# design.net
KiCad netlist of a schematic drawn in Altium Designer
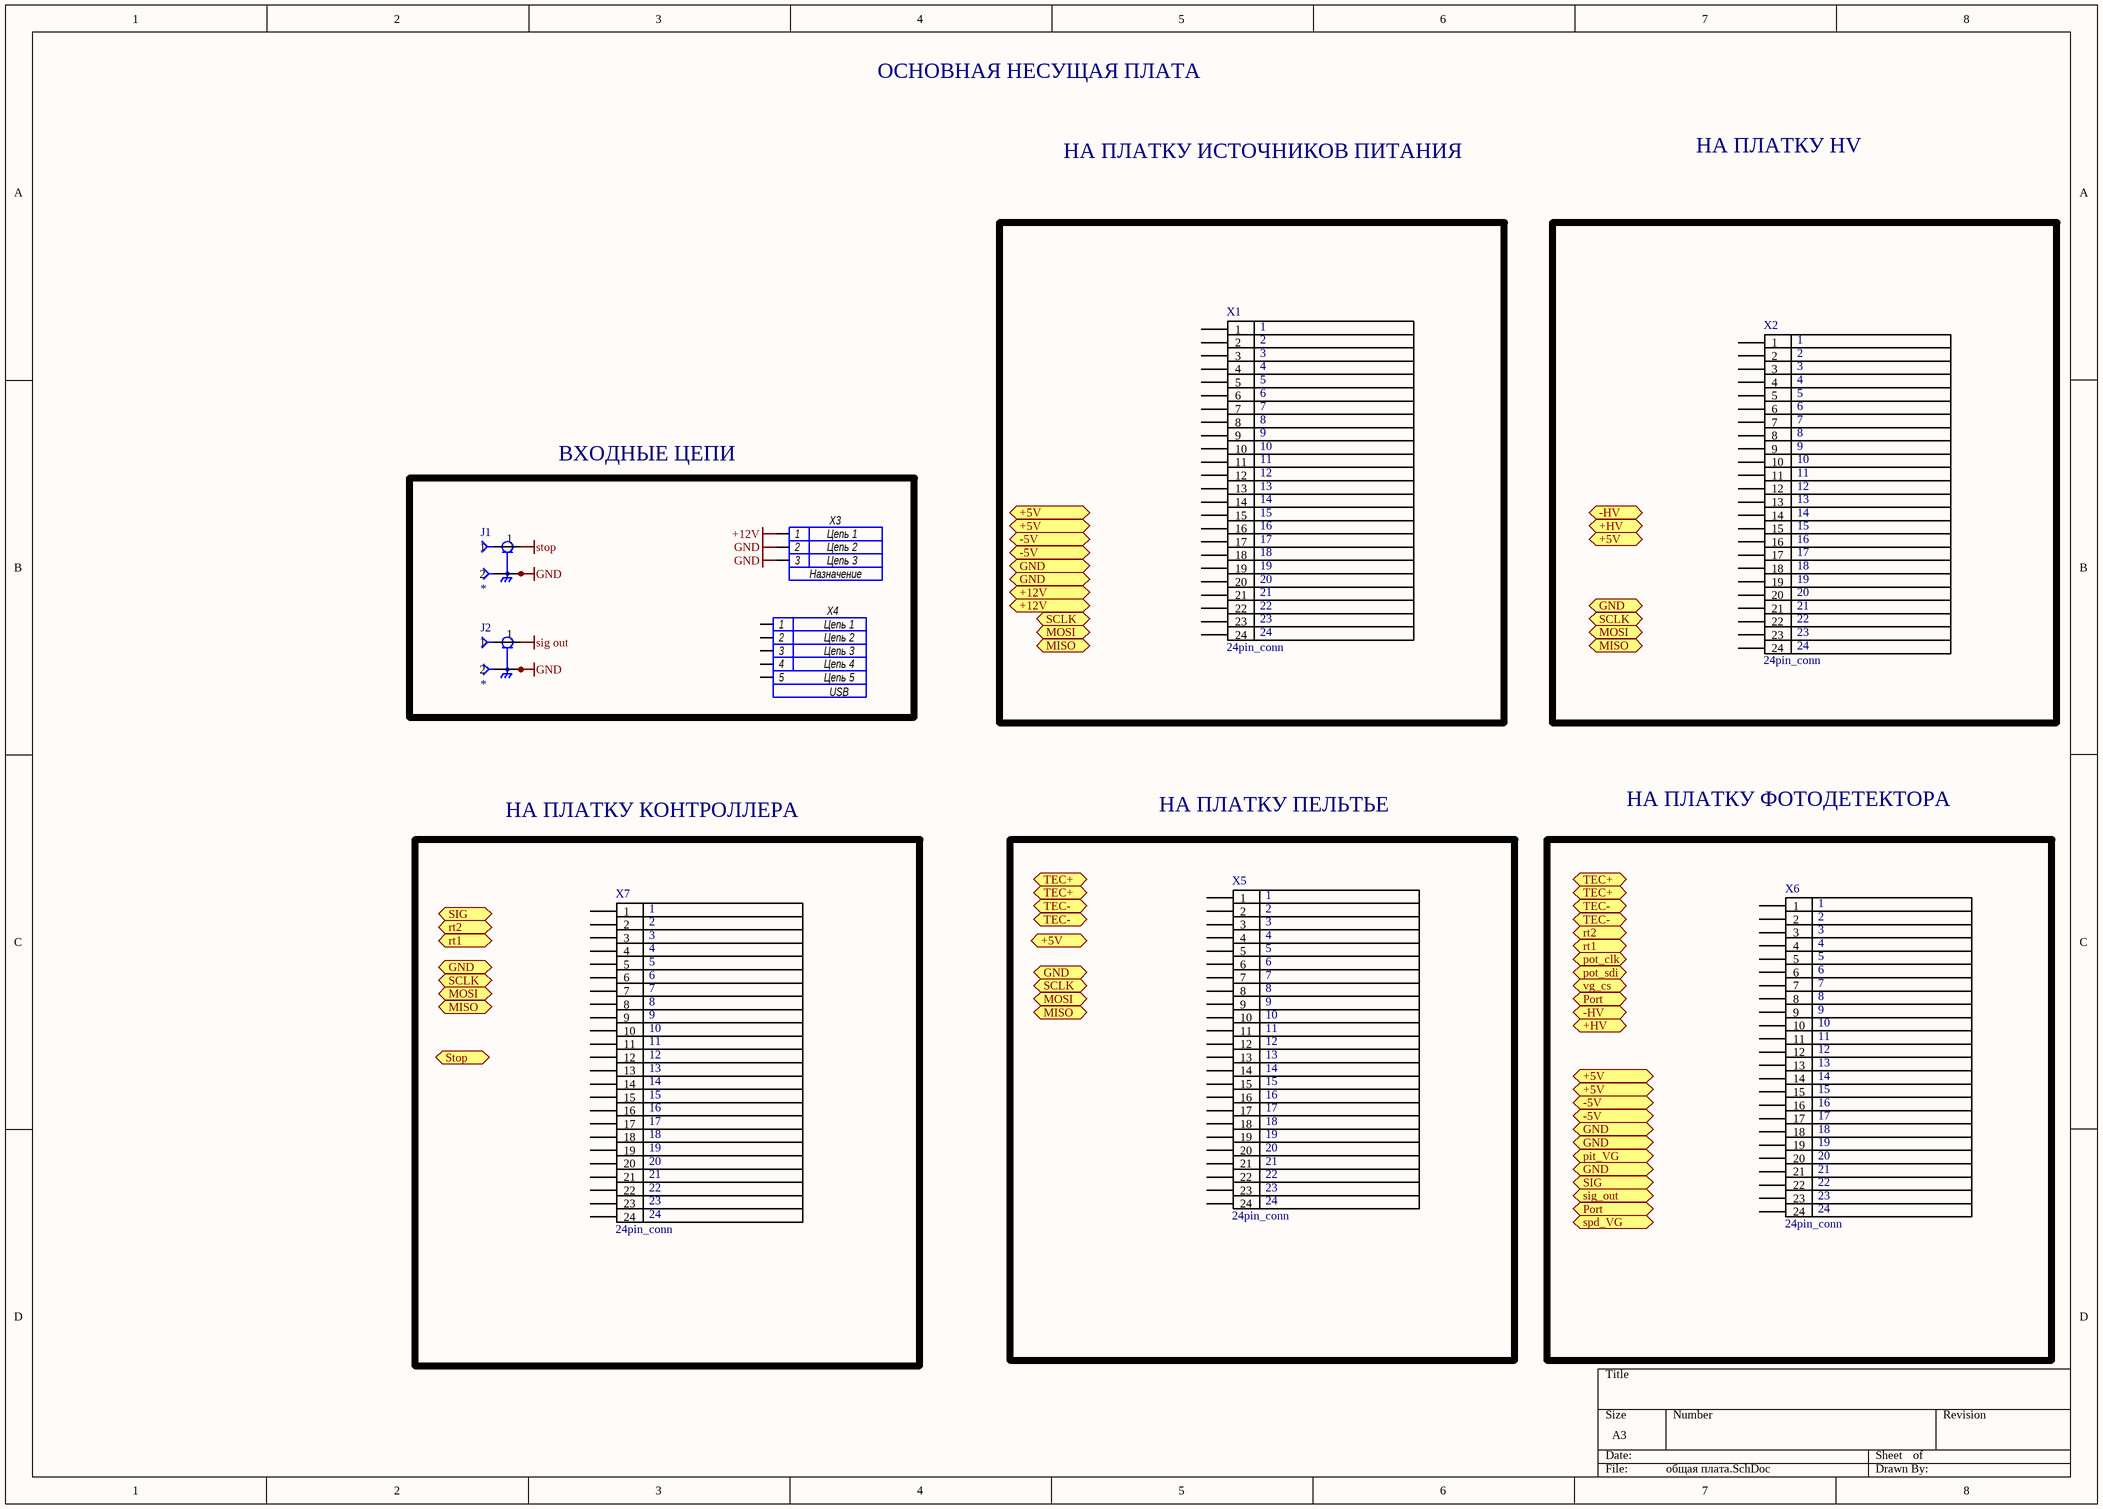
[diagram p0: общая плата.SchDoc]

(export (version "E")
  (design (tool "Eeschema 10.0.6"))
  (components
    (comp (ref "J1")
      (value "221790-1")
      (footprint "TE_221790-1")
      (description "Connector; SMA; PCB; Right Angle; Stainless Steel; 0.6 in.; Beryllium Copper")
      (fields (field (name "MF") "TE Connectivity") (field (name "COMMENT_1") "*"))
      (libsource (lib "SMA 221790-1") (part "221790-1"))
    )
    (comp (ref "J2")
      (value "221790-1")
      (footprint "TE_221790-1")
      (description "Connector; SMA; PCB; Right Angle; Stainless Steel; 0.6 in.; Beryllium Copper")
      (fields (field (name "MF") "TE Connectivity") (field (name "COMMENT_1") "*"))
      (libsource (lib "SMA 221790-1") (part "221790-1"))
    )
    (comp (ref "X1") (value "24pin_conn") (footprint "BH-24") (libsource (lib "Schlib1") (part "24pin_conn")))
    (comp (ref "X2") (value "24pin_conn") (footprint "BH-24") (libsource (lib "Schlib1") (part "24pin_conn")))
    (comp (ref "X3")
      (value "Model")
      (footprint "DC210")
      (fields
        (field (name "NET1") "Цепь 1")
        (field (name "NET2") "Цепь 2")
        (field (name "NAME") "Назначение")
        (field (name "NET3") "Цепь 3")
      )
      (libsource (lib "SCH_LIB") (part "Connector 3"))
    )
    (comp (ref "X4")
      (value "Model")
      (footprint "USB_TypeB")
      (fields
        (field (name "NET4") "Цепь 4")
        (field (name "NET1") "Цепь 1")
        (field (name "NET2") "Цепь 2")
        (field (name "NAME") "USB")
        (field (name "NET3") "Цепь 3")
        (field (name "NET5") "Цепь 5")
      )
      (libsource (lib "SCH_LIB") (part "Connector 5"))
    )
    (comp (ref "X5") (value "24pin_conn") (footprint "BH-24") (libsource (lib "Schlib1") (part "24pin_conn")))
    (comp (ref "X6") (value "24pin_conn") (footprint "BH-24") (libsource (lib "Schlib1") (part "24pin_conn")))
    (comp (ref "X7") (value "24pin_conn") (footprint "BH-24") (libsource (lib "Schlib1") (part "24pin_conn")))
  )
  (nets
    (net (code "1") (name "+12V") (class "Default")
      (node (ref "X3") (pin "1") (pinfunction "1_1") (pintype "passive"))
    )
    (net (code "22") (name "GND") (class "Default")
      (node (ref "J1") (pin "2") (pinfunction "2_2") (pintype "passive"))
      (node (ref "J1") (pin "3") (pinfunction "2_3") (pintype "passive"))
      (node (ref "J1") (pin "4") (pinfunction "2_4") (pintype "passive"))
      (node (ref "J1") (pin "5") (pinfunction "2_5") (pintype "passive"))
      (node (ref "J2") (pin "2") (pinfunction "2_2") (pintype "passive"))
      (node (ref "J2") (pin "3") (pinfunction "2_3") (pintype "passive"))
      (node (ref "J2") (pin "4") (pinfunction "2_4") (pintype "passive"))
      (node (ref "J2") (pin "5") (pinfunction "2_5") (pintype "passive"))
      (node (ref "X3") (pin "2") (pinfunction "2_2") (pintype "passive"))
      (node (ref "X3") (pin "3") (pinfunction "3_3") (pintype "passive"))
    )
    (net (code "23") (name "sig out") (class "Default")
      (node (ref "J2") (pin "1") (pinfunction "1_1") (pintype "passive"))
    )
    (net (code "24") (name "stop") (class "Default")
      (node (ref "J1") (pin "1") (pinfunction "1_1") (pintype "passive"))
    )
    (net (code "25") (name "unconnected-(X1-Pad1)") (class "Default")
      (node (ref "X1") (pin "1") (pinfunction "1_1") (pintype "passive"))
    )
    (net (code "26") (name "unconnected-(X1-Pad2)") (class "Default")
      (node (ref "X1") (pin "2") (pinfunction "2_2") (pintype "passive"))
    )
    (net (code "27") (name "unconnected-(X1-Pad3)") (class "Default")
      (node (ref "X1") (pin "3") (pinfunction "3_3") (pintype "passive"))
    )
    (net (code "28") (name "unconnected-(X1-Pad4)") (class "Default")
      (node (ref "X1") (pin "4") (pinfunction "4_4") (pintype "passive"))
    )
    (net (code "29") (name "unconnected-(X1-Pad5)") (class "Default")
      (node (ref "X1") (pin "5") (pinfunction "5_5") (pintype "passive"))
    )
    (net (code "30") (name "unconnected-(X1-Pad6)") (class "Default")
      (node (ref "X1") (pin "6") (pinfunction "6_6") (pintype "passive"))
    )
    (net (code "31") (name "unconnected-(X1-Pad7)") (class "Default")
      (node (ref "X1") (pin "7") (pinfunction "7_7") (pintype "passive"))
    )
    (net (code "32") (name "unconnected-(X1-Pad8)") (class "Default")
      (node (ref "X1") (pin "8") (pinfunction "8_8") (pintype "passive"))
    )
    (net (code "33") (name "unconnected-(X1-Pad9)") (class "Default")
      (node (ref "X1") (pin "9") (pinfunction "9_9") (pintype "passive"))
    )
    (net (code "34") (name "unconnected-(X1-Pad10)") (class "Default")
      (node (ref "X1") (pin "10") (pinfunction "10_10") (pintype "passive"))
    )
    (net (code "35") (name "unconnected-(X1-Pad11)") (class "Default")
      (node (ref "X1") (pin "11") (pinfunction "11_11") (pintype "passive"))
    )
    (net (code "36") (name "unconnected-(X1-Pad12)") (class "Default")
      (node (ref "X1") (pin "12") (pinfunction "12_12") (pintype "passive"))
    )
    (net (code "37") (name "unconnected-(X1-Pad13)") (class "Default")
      (node (ref "X1") (pin "13") (pinfunction "13_13") (pintype "passive"))
    )
    (net (code "38") (name "unconnected-(X1-Pad14)") (class "Default")
      (node (ref "X1") (pin "14") (pinfunction "14_14") (pintype "passive"))
    )
    (net (code "39") (name "unconnected-(X1-Pad15)") (class "Default")
      (node (ref "X1") (pin "15") (pinfunction "15_15") (pintype "passive"))
    )
    (net (code "40") (name "unconnected-(X1-Pad16)") (class "Default")
      (node (ref "X1") (pin "16") (pinfunction "16_16") (pintype "passive"))
    )
    (net (code "41") (name "unconnected-(X1-Pad17)") (class "Default")
      (node (ref "X1") (pin "17") (pinfunction "17_17") (pintype "passive"))
    )
    (net (code "42") (name "unconnected-(X1-Pad18)") (class "Default")
      (node (ref "X1") (pin "18") (pinfunction "18_18") (pintype "open_collector"))
    )
    (net (code "43") (name "unconnected-(X1-Pad19)") (class "Default")
      (node (ref "X1") (pin "19") (pinfunction "19_19") (pintype "passive"))
    )
    (net (code "44") (name "unconnected-(X1-Pad20)") (class "Default")
      (node (ref "X1") (pin "20") (pinfunction "20_20") (pintype "passive"))
    )
    (net (code "45") (name "unconnected-(X1-Pad21)") (class "Default")
      (node (ref "X1") (pin "21") (pinfunction "21_21") (pintype "passive"))
    )
    (net (code "46") (name "unconnected-(X1-Pad22)") (class "Default")
      (node (ref "X1") (pin "22") (pinfunction "22_22") (pintype "passive"))
    )
    (net (code "47") (name "unconnected-(X1-Pad23)") (class "Default")
      (node (ref "X1") (pin "23") (pinfunction "23_23") (pintype "passive"))
    )
    (net (code "48") (name "unconnected-(X1-Pad24)") (class "Default")
      (node (ref "X1") (pin "24") (pinfunction "24_24") (pintype "passive"))
    )
    (net (code "49") (name "unconnected-(X2-Pad1)") (class "Default")
      (node (ref "X2") (pin "1") (pinfunction "1_1") (pintype "passive"))
    )
    (net (code "50") (name "unconnected-(X2-Pad2)") (class "Default")
      (node (ref "X2") (pin "2") (pinfunction "2_2") (pintype "passive"))
    )
    (net (code "51") (name "unconnected-(X2-Pad3)") (class "Default")
      (node (ref "X2") (pin "3") (pinfunction "3_3") (pintype "passive"))
    )
    (net (code "52") (name "unconnected-(X2-Pad4)") (class "Default")
      (node (ref "X2") (pin "4") (pinfunction "4_4") (pintype "passive"))
    )
    (net (code "53") (name "unconnected-(X2-Pad5)") (class "Default")
      (node (ref "X2") (pin "5") (pinfunction "5_5") (pintype "passive"))
    )
    (net (code "54") (name "unconnected-(X2-Pad6)") (class "Default")
      (node (ref "X2") (pin "6") (pinfunction "6_6") (pintype "passive"))
    )
    (net (code "55") (name "unconnected-(X2-Pad7)") (class "Default")
      (node (ref "X2") (pin "7") (pinfunction "7_7") (pintype "passive"))
    )
    (net (code "56") (name "unconnected-(X2-Pad8)") (class "Default")
      (node (ref "X2") (pin "8") (pinfunction "8_8") (pintype "passive"))
    )
    (net (code "57") (name "unconnected-(X2-Pad9)") (class "Default")
      (node (ref "X2") (pin "9") (pinfunction "9_9") (pintype "passive"))
    )
    (net (code "58") (name "unconnected-(X2-Pad10)") (class "Default")
      (node (ref "X2") (pin "10") (pinfunction "10_10") (pintype "passive"))
    )
    (net (code "59") (name "unconnected-(X2-Pad11)") (class "Default")
      (node (ref "X2") (pin "11") (pinfunction "11_11") (pintype "passive"))
    )
    (net (code "60") (name "unconnected-(X2-Pad12)") (class "Default")
      (node (ref "X2") (pin "12") (pinfunction "12_12") (pintype "passive"))
    )
    (net (code "61") (name "unconnected-(X2-Pad13)") (class "Default")
      (node (ref "X2") (pin "13") (pinfunction "13_13") (pintype "passive"))
    )
    (net (code "62") (name "unconnected-(X2-Pad14)") (class "Default")
      (node (ref "X2") (pin "14") (pinfunction "14_14") (pintype "passive"))
    )
    (net (code "63") (name "unconnected-(X2-Pad15)") (class "Default")
      (node (ref "X2") (pin "15") (pinfunction "15_15") (pintype "passive"))
    )
    (net (code "64") (name "unconnected-(X2-Pad16)") (class "Default")
      (node (ref "X2") (pin "16") (pinfunction "16_16") (pintype "passive"))
    )
    (net (code "65") (name "unconnected-(X2-Pad17)") (class "Default")
      (node (ref "X2") (pin "17") (pinfunction "17_17") (pintype "passive"))
    )
    (net (code "66") (name "unconnected-(X2-Pad18)") (class "Default")
      (node (ref "X2") (pin "18") (pinfunction "18_18") (pintype "open_collector"))
    )
    (net (code "67") (name "unconnected-(X2-Pad19)") (class "Default")
      (node (ref "X2") (pin "19") (pinfunction "19_19") (pintype "passive"))
    )
    (net (code "68") (name "unconnected-(X2-Pad20)") (class "Default")
      (node (ref "X2") (pin "20") (pinfunction "20_20") (pintype "passive"))
    )
    (net (code "69") (name "unconnected-(X2-Pad21)") (class "Default")
      (node (ref "X2") (pin "21") (pinfunction "21_21") (pintype "passive"))
    )
    (net (code "70") (name "unconnected-(X2-Pad22)") (class "Default")
      (node (ref "X2") (pin "22") (pinfunction "22_22") (pintype "passive"))
    )
    (net (code "71") (name "unconnected-(X2-Pad23)") (class "Default")
      (node (ref "X2") (pin "23") (pinfunction "23_23") (pintype "passive"))
    )
    (net (code "72") (name "unconnected-(X2-Pad24)") (class "Default")
      (node (ref "X2") (pin "24") (pinfunction "24_24") (pintype "passive"))
    )
    (net (code "73") (name "unconnected-(X4-Pad1)") (class "Default")
      (node (ref "X4") (pin "1") (pinfunction "1_1") (pintype "passive"))
    )
    (net (code "74") (name "unconnected-(X4-Pad2)") (class "Default")
      (node (ref "X4") (pin "2") (pinfunction "2_2") (pintype "passive"))
    )
    (net (code "75") (name "unconnected-(X4-Pad3)") (class "Default")
      (node (ref "X4") (pin "3") (pinfunction "3_3") (pintype "passive"))
    )
    (net (code "76") (name "unconnected-(X4-Pad4)") (class "Default")
      (node (ref "X4") (pin "4") (pinfunction "4_4") (pintype "passive"))
    )
    (net (code "77") (name "unconnected-(X4-Pad5)") (class "Default")
      (node (ref "X4") (pin "5") (pinfunction "5_5") (pintype "passive"))
    )
    (net (code "78") (name "unconnected-(X5-Pad1)") (class "Default")
      (node (ref "X5") (pin "1") (pinfunction "1_1") (pintype "passive"))
    )
    (net (code "79") (name "unconnected-(X5-Pad2)") (class "Default")
      (node (ref "X5") (pin "2") (pinfunction "2_2") (pintype "passive"))
    )
    (net (code "80") (name "unconnected-(X5-Pad3)") (class "Default")
      (node (ref "X5") (pin "3") (pinfunction "3_3") (pintype "passive"))
    )
    (net (code "81") (name "unconnected-(X5-Pad4)") (class "Default")
      (node (ref "X5") (pin "4") (pinfunction "4_4") (pintype "passive"))
    )
    (net (code "82") (name "unconnected-(X5-Pad5)") (class "Default")
      (node (ref "X5") (pin "5") (pinfunction "5_5") (pintype "passive"))
    )
    (net (code "83") (name "unconnected-(X5-Pad6)") (class "Default")
      (node (ref "X5") (pin "6") (pinfunction "6_6") (pintype "passive"))
    )
    (net (code "84") (name "unconnected-(X5-Pad7)") (class "Default")
      (node (ref "X5") (pin "7") (pinfunction "7_7") (pintype "passive"))
    )
    (net (code "85") (name "unconnected-(X5-Pad8)") (class "Default")
      (node (ref "X5") (pin "8") (pinfunction "8_8") (pintype "passive"))
    )
    (net (code "86") (name "unconnected-(X5-Pad9)") (class "Default")
      (node (ref "X5") (pin "9") (pinfunction "9_9") (pintype "passive"))
    )
    (net (code "87") (name "unconnected-(X5-Pad10)") (class "Default")
      (node (ref "X5") (pin "10") (pinfunction "10_10") (pintype "passive"))
    )
    (net (code "88") (name "unconnected-(X5-Pad11)") (class "Default")
      (node (ref "X5") (pin "11") (pinfunction "11_11") (pintype "passive"))
    )
    (net (code "89") (name "unconnected-(X5-Pad12)") (class "Default")
      (node (ref "X5") (pin "12") (pinfunction "12_12") (pintype "passive"))
    )
    (net (code "90") (name "unconnected-(X5-Pad13)") (class "Default")
      (node (ref "X5") (pin "13") (pinfunction "13_13") (pintype "passive"))
    )
    (net (code "91") (name "unconnected-(X5-Pad14)") (class "Default")
      (node (ref "X5") (pin "14") (pinfunction "14_14") (pintype "passive"))
    )
    (net (code "92") (name "unconnected-(X5-Pad15)") (class "Default")
      (node (ref "X5") (pin "15") (pinfunction "15_15") (pintype "passive"))
    )
    (net (code "93") (name "unconnected-(X5-Pad16)") (class "Default")
      (node (ref "X5") (pin "16") (pinfunction "16_16") (pintype "passive"))
    )
    (net (code "94") (name "unconnected-(X5-Pad17)") (class "Default")
      (node (ref "X5") (pin "17") (pinfunction "17_17") (pintype "passive"))
    )
    (net (code "95") (name "unconnected-(X5-Pad18)") (class "Default")
      (node (ref "X5") (pin "18") (pinfunction "18_18") (pintype "open_collector"))
    )
    (net (code "96") (name "unconnected-(X5-Pad19)") (class "Default")
      (node (ref "X5") (pin "19") (pinfunction "19_19") (pintype "passive"))
    )
    (net (code "97") (name "unconnected-(X5-Pad20)") (class "Default")
      (node (ref "X5") (pin "20") (pinfunction "20_20") (pintype "passive"))
    )
    (net (code "98") (name "unconnected-(X5-Pad21)") (class "Default")
      (node (ref "X5") (pin "21") (pinfunction "21_21") (pintype "passive"))
    )
    (net (code "99") (name "unconnected-(X5-Pad22)") (class "Default")
      (node (ref "X5") (pin "22") (pinfunction "22_22") (pintype "passive"))
    )
    (net (code "100") (name "unconnected-(X5-Pad23)") (class "Default")
      (node (ref "X5") (pin "23") (pinfunction "23_23") (pintype "passive"))
    )
    (net (code "101") (name "unconnected-(X5-Pad24)") (class "Default")
      (node (ref "X5") (pin "24") (pinfunction "24_24") (pintype "passive"))
    )
    (net (code "102") (name "unconnected-(X6-Pad1)") (class "Default")
      (node (ref "X6") (pin "1") (pinfunction "1_1") (pintype "passive"))
    )
    (net (code "103") (name "unconnected-(X6-Pad2)") (class "Default")
      (node (ref "X6") (pin "2") (pinfunction "2_2") (pintype "passive"))
    )
    (net (code "104") (name "unconnected-(X6-Pad3)") (class "Default")
      (node (ref "X6") (pin "3") (pinfunction "3_3") (pintype "passive"))
    )
    (net (code "105") (name "unconnected-(X6-Pad4)") (class "Default")
      (node (ref "X6") (pin "4") (pinfunction "4_4") (pintype "passive"))
    )
    (net (code "106") (name "unconnected-(X6-Pad5)") (class "Default")
      (node (ref "X6") (pin "5") (pinfunction "5_5") (pintype "passive"))
    )
    (net (code "107") (name "unconnected-(X6-Pad6)") (class "Default")
      (node (ref "X6") (pin "6") (pinfunction "6_6") (pintype "passive"))
    )
    (net (code "108") (name "unconnected-(X6-Pad7)") (class "Default")
      (node (ref "X6") (pin "7") (pinfunction "7_7") (pintype "passive"))
    )
    (net (code "109") (name "unconnected-(X6-Pad8)") (class "Default")
      (node (ref "X6") (pin "8") (pinfunction "8_8") (pintype "passive"))
    )
    (net (code "110") (name "unconnected-(X6-Pad9)") (class "Default")
      (node (ref "X6") (pin "9") (pinfunction "9_9") (pintype "passive"))
    )
    (net (code "111") (name "unconnected-(X6-Pad10)") (class "Default")
      (node (ref "X6") (pin "10") (pinfunction "10_10") (pintype "passive"))
    )
    (net (code "112") (name "unconnected-(X6-Pad11)") (class "Default")
      (node (ref "X6") (pin "11") (pinfunction "11_11") (pintype "passive"))
    )
    (net (code "113") (name "unconnected-(X6-Pad12)") (class "Default")
      (node (ref "X6") (pin "12") (pinfunction "12_12") (pintype "passive"))
    )
    (net (code "114") (name "unconnected-(X6-Pad13)") (class "Default")
      (node (ref "X6") (pin "13") (pinfunction "13_13") (pintype "passive"))
    )
    (net (code "115") (name "unconnected-(X6-Pad14)") (class "Default")
      (node (ref "X6") (pin "14") (pinfunction "14_14") (pintype "passive"))
    )
    (net (code "116") (name "unconnected-(X6-Pad15)") (class "Default")
      (node (ref "X6") (pin "15") (pinfunction "15_15") (pintype "passive"))
    )
    (net (code "117") (name "unconnected-(X6-Pad16)") (class "Default")
      (node (ref "X6") (pin "16") (pinfunction "16_16") (pintype "passive"))
    )
    (net (code "118") (name "unconnected-(X6-Pad17)") (class "Default")
      (node (ref "X6") (pin "17") (pinfunction "17_17") (pintype "passive"))
    )
    (net (code "119") (name "unconnected-(X6-Pad18)") (class "Default")
      (node (ref "X6") (pin "18") (pinfunction "18_18") (pintype "open_collector"))
    )
    (net (code "120") (name "unconnected-(X6-Pad19)") (class "Default")
      (node (ref "X6") (pin "19") (pinfunction "19_19") (pintype "passive"))
    )
    (net (code "121") (name "unconnected-(X6-Pad20)") (class "Default")
      (node (ref "X6") (pin "20") (pinfunction "20_20") (pintype "passive"))
    )
    (net (code "122") (name "unconnected-(X6-Pad21)") (class "Default")
      (node (ref "X6") (pin "21") (pinfunction "21_21") (pintype "passive"))
    )
    (net (code "123") (name "unconnected-(X6-Pad22)") (class "Default")
      (node (ref "X6") (pin "22") (pinfunction "22_22") (pintype "passive"))
    )
    (net (code "124") (name "unconnected-(X6-Pad23)") (class "Default")
      (node (ref "X6") (pin "23") (pinfunction "23_23") (pintype "passive"))
    )
    (net (code "125") (name "unconnected-(X6-Pad24)") (class "Default")
      (node (ref "X6") (pin "24") (pinfunction "24_24") (pintype "passive"))
    )
    (net (code "126") (name "unconnected-(X7-Pad1)") (class "Default")
      (node (ref "X7") (pin "1") (pinfunction "1_1") (pintype "passive"))
    )
    (net (code "127") (name "unconnected-(X7-Pad2)") (class "Default")
      (node (ref "X7") (pin "2") (pinfunction "2_2") (pintype "passive"))
    )
    (net (code "128") (name "unconnected-(X7-Pad3)") (class "Default")
      (node (ref "X7") (pin "3") (pinfunction "3_3") (pintype "passive"))
    )
    (net (code "129") (name "unconnected-(X7-Pad4)") (class "Default")
      (node (ref "X7") (pin "4") (pinfunction "4_4") (pintype "passive"))
    )
    (net (code "130") (name "unconnected-(X7-Pad5)") (class "Default")
      (node (ref "X7") (pin "5") (pinfunction "5_5") (pintype "passive"))
    )
    (net (code "131") (name "unconnected-(X7-Pad6)") (class "Default")
      (node (ref "X7") (pin "6") (pinfunction "6_6") (pintype "passive"))
    )
    (net (code "132") (name "unconnected-(X7-Pad7)") (class "Default")
      (node (ref "X7") (pin "7") (pinfunction "7_7") (pintype "passive"))
    )
    (net (code "133") (name "unconnected-(X7-Pad8)") (class "Default")
      (node (ref "X7") (pin "8") (pinfunction "8_8") (pintype "passive"))
    )
    (net (code "134") (name "unconnected-(X7-Pad9)") (class "Default")
      (node (ref "X7") (pin "9") (pinfunction "9_9") (pintype "passive"))
    )
    (net (code "135") (name "unconnected-(X7-Pad10)") (class "Default")
      (node (ref "X7") (pin "10") (pinfunction "10_10") (pintype "passive"))
    )
    (net (code "136") (name "unconnected-(X7-Pad11)") (class "Default")
      (node (ref "X7") (pin "11") (pinfunction "11_11") (pintype "passive"))
    )
    (net (code "137") (name "unconnected-(X7-Pad12)") (class "Default")
      (node (ref "X7") (pin "12") (pinfunction "12_12") (pintype "passive"))
    )
    (net (code "138") (name "unconnected-(X7-Pad13)") (class "Default")
      (node (ref "X7") (pin "13") (pinfunction "13_13") (pintype "passive"))
    )
    (net (code "139") (name "unconnected-(X7-Pad14)") (class "Default")
      (node (ref "X7") (pin "14") (pinfunction "14_14") (pintype "passive"))
    )
    (net (code "140") (name "unconnected-(X7-Pad15)") (class "Default")
      (node (ref "X7") (pin "15") (pinfunction "15_15") (pintype "passive"))
    )
    (net (code "141") (name "unconnected-(X7-Pad16)") (class "Default")
      (node (ref "X7") (pin "16") (pinfunction "16_16") (pintype "passive"))
    )
    (net (code "142") (name "unconnected-(X7-Pad17)") (class "Default")
      (node (ref "X7") (pin "17") (pinfunction "17_17") (pintype "passive"))
    )
    (net (code "143") (name "unconnected-(X7-Pad18)") (class "Default")
      (node (ref "X7") (pin "18") (pinfunction "18_18") (pintype "open_collector"))
    )
    (net (code "144") (name "unconnected-(X7-Pad19)") (class "Default")
      (node (ref "X7") (pin "19") (pinfunction "19_19") (pintype "passive"))
    )
    (net (code "145") (name "unconnected-(X7-Pad20)") (class "Default")
      (node (ref "X7") (pin "20") (pinfunction "20_20") (pintype "passive"))
    )
    (net (code "146") (name "unconnected-(X7-Pad21)") (class "Default")
      (node (ref "X7") (pin "21") (pinfunction "21_21") (pintype "passive"))
    )
    (net (code "147") (name "unconnected-(X7-Pad22)") (class "Default")
      (node (ref "X7") (pin "22") (pinfunction "22_22") (pintype "passive"))
    )
    (net (code "148") (name "unconnected-(X7-Pad23)") (class "Default")
      (node (ref "X7") (pin "23") (pinfunction "23_23") (pintype "passive"))
    )
    (net (code "149") (name "unconnected-(X7-Pad24)") (class "Default")
      (node (ref "X7") (pin "24") (pinfunction "24_24") (pintype "passive"))
    )
  )
)
